# CANx.net
KiCad netlist of a schematic drawn in EAGLE
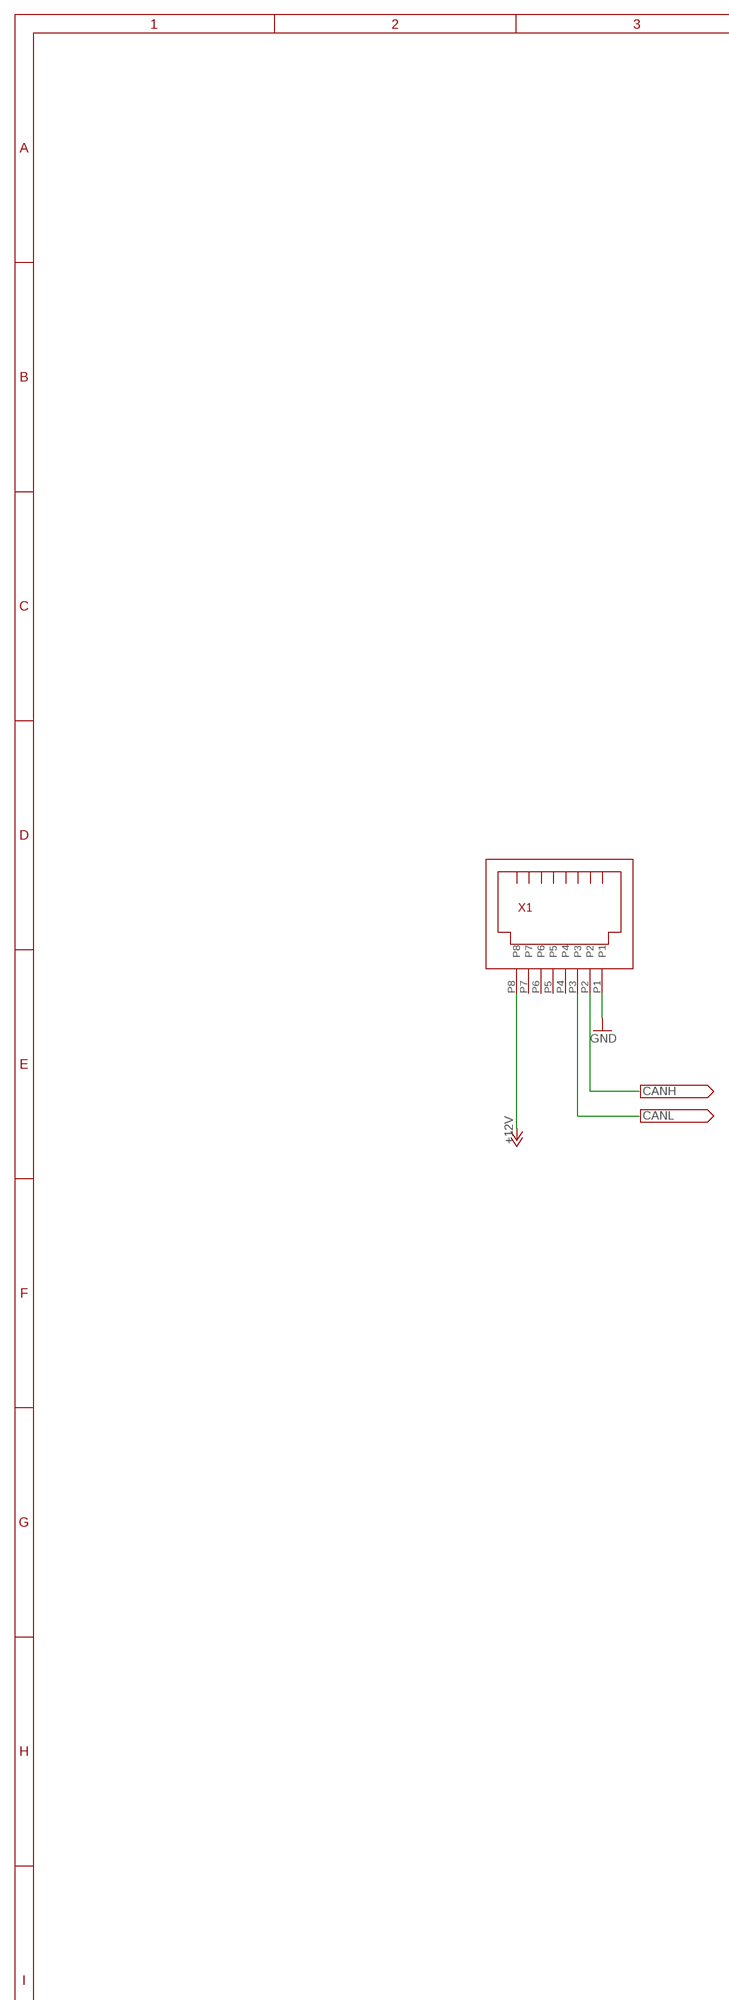
[diagram p0: schematic, sheet 1, part 1 of 2]
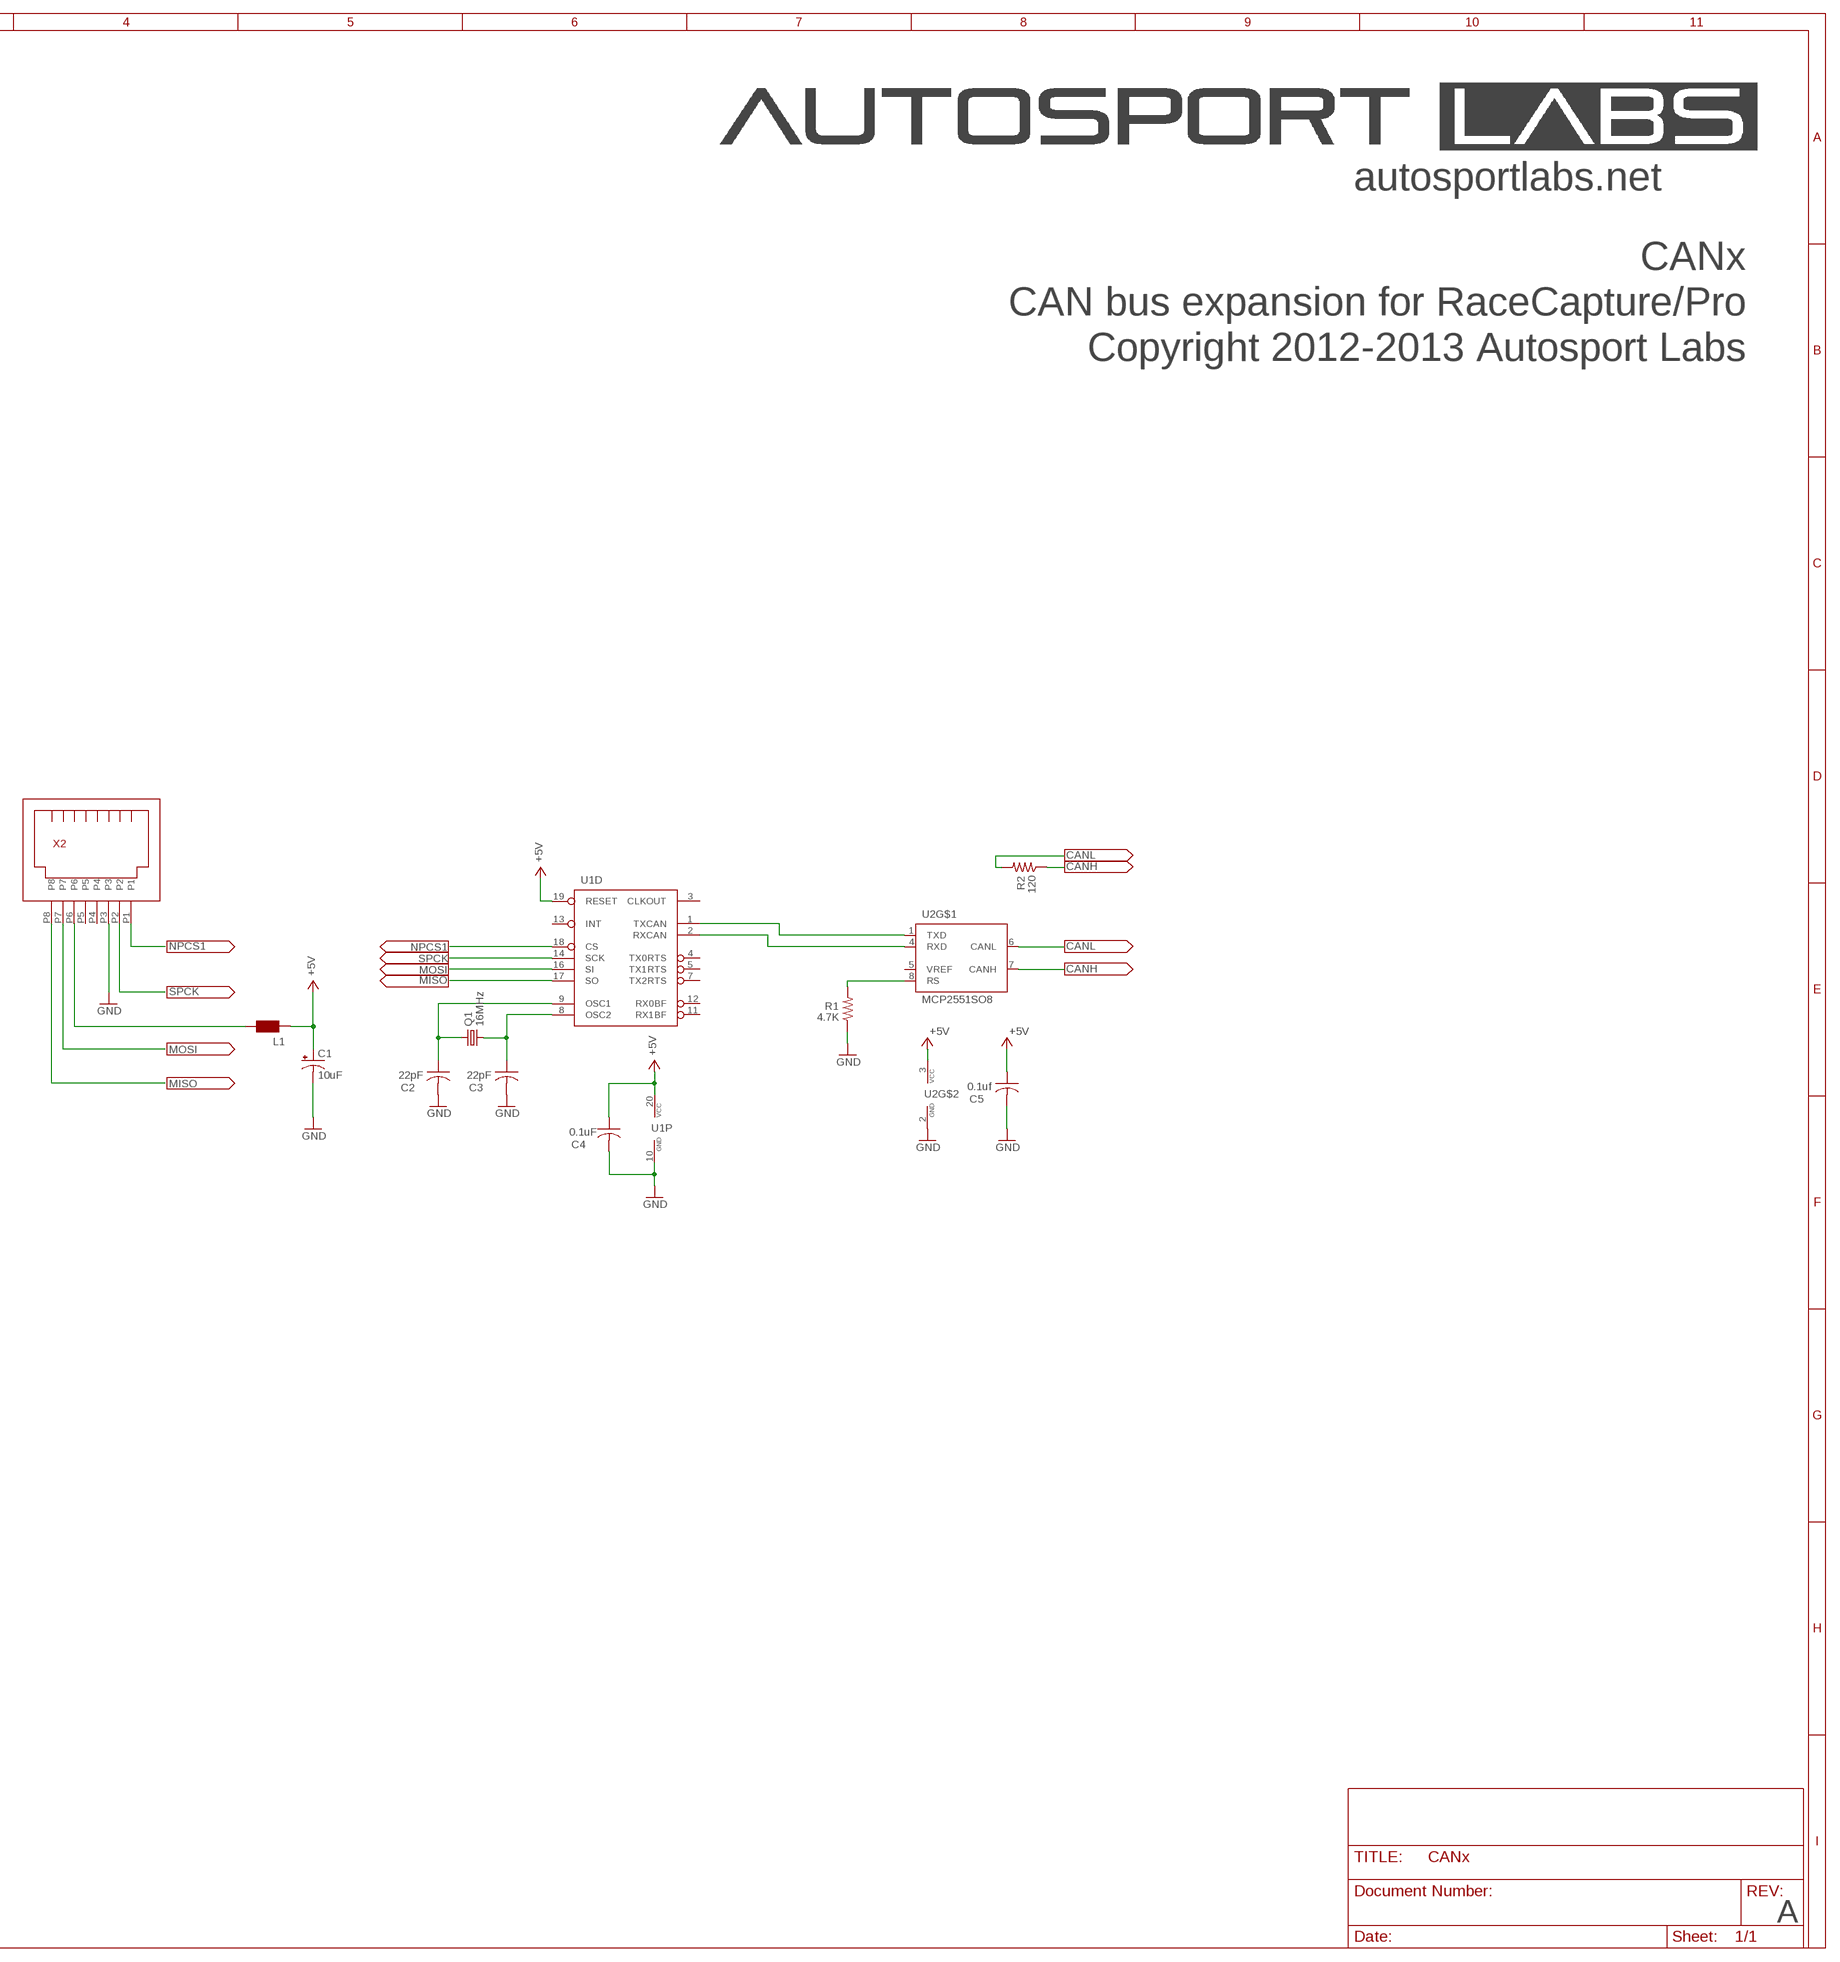
[diagram p1: schematic, sheet 1, part 2 of 2]

(export (version "E")
  (design (tool "Eeschema 10.0.6"))
  (components
    (comp (ref "C1")
      (value "10uF")
      (footprint "eagle-import:SMC_D")
      (libsource (lib "eagle-import") (part "CPOL-USSMCD"))
    )
    (comp (ref "C2")
      (value "22pF")
      (footprint "eagle-import:C0603K")
      (libsource (lib "eagle-import") (part "C-USC0603K"))
    )
    (comp (ref "C3")
      (value "22pF")
      (footprint "eagle-import:C0603K")
      (libsource (lib "eagle-import") (part "C-USC0603K"))
    )
    (comp (ref "C4")
      (value "0.1uF")
      (footprint "eagle-import:C0603K")
      (libsource (lib "eagle-import") (part "C-USC0603K"))
    )
    (comp (ref "C5")
      (value "0.1uf")
      (footprint "eagle-import:C0603K")
      (libsource (lib "eagle-import") (part "C-USC0603K"))
    )
    (comp (ref "L1")
      (value "WE-CBF_1812")
      (footprint "eagle-import:1812")
      (libsource (lib "eagle-import") (part "WE-CBF_1812"))
    )
    (comp (ref "Q1")
      (value "16MHz")
      (footprint "eagle-import:CRYSTAL-SMD-5X3")
      (libsource (lib "eagle-import") (part "CRYSTAL5X3"))
    )
    (comp (ref "R1")
      (value "4.7K")
      (footprint "eagle-import:R0603")
      (libsource (lib "eagle-import") (part "R-US_R0603"))
    )
    (comp (ref "R2")
      (value "120")
      (footprint "eagle-import:R0603")
      (libsource (lib "eagle-import") (part "R-US_R0603"))
    )
    (comp (ref "U1")
      (value "MCP2515ST")
      (footprint "eagle-import:TSSOP20")
      (libsource (lib "eagle-import") (part "MCP2515ST"))
    )
    (comp (ref "U2")
      (value "MCP2551SO8")
      (footprint "eagle-import:SO08")
      (libsource (lib "eagle-import") (part "MCP2551SO8"))
    )
    (comp (ref "X1")
      (value "RJ45_RIGHT_ANGLEMOLEX_95001-2881")
      (footprint "eagle-import:RJ45_RIGHT_ANGLE_MOLEX_95001-2881")
      (libsource (lib "eagle-import") (part "RJ45_RIGHT_ANGLEMOLEX_95001-2881"))
    )
    (comp (ref "X2")
      (value "RJ45_RIGHT_ANGLEMOLEX_95001-2881")
      (footprint "eagle-import:RJ45_RIGHT_ANGLE_MOLEX_95001-2881")
      (libsource (lib "eagle-import") (part "RJ45_RIGHT_ANGLEMOLEX_95001-2881"))
    )
  )
  (nets
    (net (code "1") (name "+5V") (class "Default")
      (node (ref "C1") (pin "+") (pinfunction "+_+") (pintype "passive"))
      (node (ref "C4") (pin "1") (pinfunction "1_1") (pintype "passive"))
      (node (ref "C5") (pin "1") (pinfunction "1_1") (pintype "passive"))
      (node (ref "L1") (pin "1") (pinfunction "1_1") (pintype "passive"))
      (node (ref "U1") (pin "19") (pinfunction "RESET_19") (pintype "input"))
      (node (ref "U1") (pin "20") (pinfunction "VCC_20") (pintype "power_in"))
      (node (ref "U2") (pin "3") (pinfunction "VCC_3") (pintype "power_in"))
    )
    (net (code "2") (name "+12V") (class "Default")
      (node (ref "X1") (pin "P8") (pinfunction "P8_P8") (pintype "bidirectional"))
    )
    (net (code "3") (name "/CANH") (class "Default")
      (node (ref "R2") (pin "1") (pinfunction "1_1") (pintype "passive"))
      (node (ref "U2") (pin "7") (pinfunction "CANH_7") (pintype "bidirectional"))
      (node (ref "X1") (pin "P2") (pinfunction "P2_P2") (pintype "bidirectional"))
    )
    (net (code "4") (name "/CANL") (class "Default")
      (node (ref "R2") (pin "2") (pinfunction "2_2") (pintype "passive"))
      (node (ref "U2") (pin "6") (pinfunction "CANL_6") (pintype "bidirectional"))
      (node (ref "X1") (pin "P3") (pinfunction "P3_P3") (pintype "bidirectional"))
    )
    (net (code "5") (name "/MISO") (class "Default")
      (node (ref "U1") (pin "17") (pinfunction "SO_17") (pintype "output"))
      (node (ref "X2") (pin "P8") (pinfunction "P8_P8") (pintype "bidirectional"))
    )
    (net (code "6") (name "/MOSI") (class "Default")
      (node (ref "U1") (pin "16") (pinfunction "SI_16") (pintype "input"))
      (node (ref "X2") (pin "P7") (pinfunction "P7_P7") (pintype "bidirectional"))
    )
    (net (code "7") (name "/NPCS1") (class "Default")
      (node (ref "U1") (pin "18") (pinfunction "CS_18") (pintype "input"))
      (node (ref "X2") (pin "P1") (pinfunction "P1_P1") (pintype "bidirectional"))
    )
    (net (code "8") (name "/SPCK") (class "Default")
      (node (ref "U1") (pin "14") (pinfunction "SCK_14") (pintype "input"))
      (node (ref "X2") (pin "P2") (pinfunction "P2_P2") (pintype "bidirectional"))
    )
    (net (code "9") (name "GND") (class "Default")
      (node (ref "C1") (pin "-") (pinfunction "-_-") (pintype "passive"))
      (node (ref "C2") (pin "2") (pinfunction "2_2") (pintype "passive"))
      (node (ref "C3") (pin "2") (pinfunction "2_2") (pintype "passive"))
      (node (ref "C4") (pin "2") (pinfunction "2_2") (pintype "passive"))
      (node (ref "C5") (pin "2") (pinfunction "2_2") (pintype "passive"))
      (node (ref "R1") (pin "1") (pinfunction "1_1") (pintype "passive"))
      (node (ref "U1") (pin "10") (pinfunction "GND_10") (pintype "power_in"))
      (node (ref "U2") (pin "2") (pinfunction "GND_2") (pintype "power_in"))
      (node (ref "X1") (pin "P1") (pinfunction "P1_P1") (pintype "bidirectional"))
      (node (ref "X2") (pin "P3") (pinfunction "P3_P3") (pintype "bidirectional"))
    )
    (net (code "10") (name "Net-(L1-Pad2)") (class "Default")
      (node (ref "L1") (pin "2") (pinfunction "2_2") (pintype "passive"))
      (node (ref "X2") (pin "P6") (pinfunction "P6_P6") (pintype "bidirectional"))
    )
    (net (code "11") (name "Net-(Q1-2)") (class "Default")
      (node (ref "C2") (pin "1") (pinfunction "1_1") (pintype "passive"))
      (node (ref "Q1") (pin "3") (pinfunction "2_3") (pintype "passive"))
      (node (ref "U1") (pin "9") (pinfunction "OSC1_9") (pintype "input"))
    )
    (net (code "12") (name "Net-(U1A-OSC2)") (class "Default")
      (node (ref "C3") (pin "1") (pinfunction "1_1") (pintype "passive"))
      (node (ref "Q1") (pin "1") (pinfunction "1_1") (pintype "passive"))
      (node (ref "U1") (pin "8") (pinfunction "OSC2_8") (pintype "input"))
    )
    (net (code "13") (name "Net-(U1A-RXCAN)") (class "Default")
      (node (ref "U1") (pin "2") (pinfunction "RXCAN_2") (pintype "input"))
      (node (ref "U2") (pin "4") (pinfunction "RXD_4") (pintype "bidirectional"))
    )
    (net (code "14") (name "Net-(U1A-TXCAN)") (class "Default")
      (node (ref "U1") (pin "1") (pinfunction "TXCAN_1") (pintype "output"))
      (node (ref "U2") (pin "1") (pinfunction "TXD_1") (pintype "bidirectional"))
    )
    (net (code "15") (name "Net-(U2A-RS)") (class "Default")
      (node (ref "R1") (pin "2") (pinfunction "2_2") (pintype "passive"))
      (node (ref "U2") (pin "8") (pinfunction "RS_8") (pintype "bidirectional"))
    )
    (net (code "16") (name "unconnected-(U1A-CLKOUT-Pad3)") (class "Default")
      (node (ref "U1") (pin "3") (pinfunction "CLKOUT_3") (pintype "output"))
    )
    (net (code "17") (name "unconnected-(U1A-INT-Pad13)") (class "Default")
      (node (ref "U1") (pin "13") (pinfunction "INT_13") (pintype "output"))
    )
    (net (code "18") (name "unconnected-(U1A-RX0BF-Pad12)") (class "Default")
      (node (ref "U1") (pin "12") (pinfunction "RX0BF_12") (pintype "output"))
    )
    (net (code "19") (name "unconnected-(U1A-RX1BF-Pad11)") (class "Default")
      (node (ref "U1") (pin "11") (pinfunction "RX1BF_11") (pintype "output"))
    )
    (net (code "20") (name "unconnected-(U1A-TX0RTS-Pad4)") (class "Default")
      (node (ref "U1") (pin "4") (pinfunction "TX0RTS_4") (pintype "input"))
    )
    (net (code "21") (name "unconnected-(U1A-TX1RTS-Pad5)") (class "Default")
      (node (ref "U1") (pin "5") (pinfunction "TX1RTS_5") (pintype "input"))
    )
    (net (code "22") (name "unconnected-(U1A-TX2RTS-Pad7)") (class "Default")
      (node (ref "U1") (pin "7") (pinfunction "TX2RTS_7") (pintype "input"))
    )
    (net (code "23") (name "unconnected-(U2A-VREF-Pad5)") (class "Default")
      (node (ref "U2") (pin "5") (pinfunction "VREF_5") (pintype "bidirectional"))
    )
    (net (code "24") (name "unconnected-(X1-PadP4)") (class "Default")
      (node (ref "X1") (pin "P4") (pinfunction "P4_P4") (pintype "bidirectional"))
    )
    (net (code "25") (name "unconnected-(X1-PadP5)") (class "Default")
      (node (ref "X1") (pin "P5") (pinfunction "P5_P5") (pintype "bidirectional"))
    )
    (net (code "26") (name "unconnected-(X1-PadP6)") (class "Default")
      (node (ref "X1") (pin "P6") (pinfunction "P6_P6") (pintype "bidirectional"))
    )
    (net (code "27") (name "unconnected-(X1-PadP7)") (class "Default")
      (node (ref "X1") (pin "P7") (pinfunction "P7_P7") (pintype "bidirectional"))
    )
    (net (code "28") (name "unconnected-(X2-PadP4)") (class "Default")
      (node (ref "X2") (pin "P4") (pinfunction "P4_P4") (pintype "bidirectional"))
    )
    (net (code "29") (name "unconnected-(X2-PadP5)") (class "Default")
      (node (ref "X2") (pin "P5") (pinfunction "P5_P5") (pintype "bidirectional"))
    )
  )
)
